# ADC.net
KiCad netlist of a schematic drawn in Altium Designer
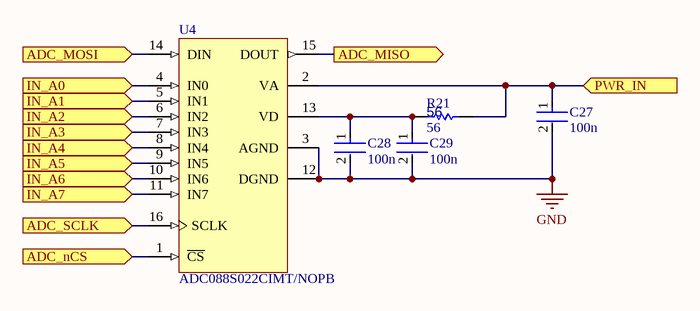
[diagram p0: ADC.SchDoc]

(export (version "E")
  (design (tool "Eeschema 10.0.6"))
  (components
    (comp (ref "C27")
      (value "100n")
      (footprint "FP-0402-L_1_0_0_05-W_0_5-IPC_A")
      (description "LARGE PADS, 0402 CAP, CHANGE COMMENT TO MATCH REAL P/N")
      (libsource (lib "Space Concordia") (part "b4654b650e69147ec39a6b967a45e02"))
    )
    (comp (ref "C28")
      (value "100n")
      (footprint "FP-0402-L_1_0_0_05-W_0_5-IPC_A")
      (description "LARGE PADS, 0402 CAP, CHANGE COMMENT TO MATCH REAL P/N")
      (libsource (lib "Space Concordia") (part "b4654b650e69147ec39a6b967a45e02"))
    )
    (comp (ref "C29")
      (value "100n")
      (footprint "FP-0402-L_1_0_0_05-W_0_5-IPC_A")
      (description "LARGE PADS, 0402 CAP, CHANGE COMMENT TO MATCH REAL P/N")
      (libsource (lib "Space Concordia") (part "b4654b650e69147ec39a6b967a45e02"))
    )
    (comp (ref "R21")
      (value "56")
      (footprint "R0603B")
      (description "Resistor")
      (fields (field (name "ALTIUM_VALUE") "56"))
      (libsource (lib "Space Concordia") (part "Resistor"))
    )
    (comp (ref "U4")
      (value "ADC088S022CIMT/NOPB")
      (footprint "MTC16_L")
      (description "8-Channel, 50 kSPS to 200 kSPS, 8-Bit A/D Converter, 16-pin TSSOP, Pb-Free")
      (fields (field (name "MANUFACTURER") "National Semiconductor"))
      (libsource (lib "Altium Content Vault") (part "CON-ADC-ADC108S052CIMT"))
    )
  )
  (nets
    (net (code "1") (name "/ADC_MISO") (class "Default")
      (node (ref "U4") (pin "15") (pinfunction "DOUT_15") (pintype "output"))
    )
    (net (code "2") (name "/ADC_MOSI") (class "Default")
      (node (ref "U4") (pin "14") (pinfunction "DIN_14") (pintype "input"))
    )
    (net (code "3") (name "/ADC_SCLK") (class "Default")
      (node (ref "U4") (pin "16") (pinfunction "SCLK_16") (pintype "input"))
    )
    (net (code "4") (name "/ADC_nCS") (class "Default")
      (node (ref "U4") (pin "1") (pinfunction "~{CS}_1") (pintype "input"))
    )
    (net (code "5") (name "/IN_A0") (class "Default")
      (node (ref "U4") (pin "4") (pinfunction "IN0_4") (pintype "input"))
    )
    (net (code "6") (name "/IN_A1") (class "Default")
      (node (ref "U4") (pin "5") (pinfunction "IN1_5") (pintype "input"))
    )
    (net (code "7") (name "/IN_A2") (class "Default")
      (node (ref "U4") (pin "6") (pinfunction "IN2_6") (pintype "input"))
    )
    (net (code "8") (name "/IN_A3") (class "Default")
      (node (ref "U4") (pin "7") (pinfunction "IN3_7") (pintype "input"))
    )
    (net (code "9") (name "/IN_A4") (class "Default")
      (node (ref "U4") (pin "8") (pinfunction "IN4_8") (pintype "input"))
    )
    (net (code "10") (name "/IN_A5") (class "Default")
      (node (ref "U4") (pin "9") (pinfunction "IN5_9") (pintype "input"))
    )
    (net (code "11") (name "/IN_A6") (class "Default")
      (node (ref "U4") (pin "10") (pinfunction "IN6_10") (pintype "input"))
    )
    (net (code "12") (name "/IN_A7") (class "Default")
      (node (ref "U4") (pin "11") (pinfunction "IN7_11") (pintype "input"))
    )
    (net (code "13") (name "/PWR_IN") (class "Default")
      (node (ref "C27") (pin "1") (pinfunction "1_1") (pintype "passive"))
      (node (ref "R21") (pin "1") (pinfunction "1_1") (pintype "passive"))
      (node (ref "U4") (pin "2") (pinfunction "VA_2") (pintype "power_in"))
    )
    (net (code "14") (name "GND") (class "Default")
      (node (ref "C27") (pin "2") (pinfunction "2_2") (pintype "passive"))
      (node (ref "C28") (pin "2") (pinfunction "2_2") (pintype "passive"))
      (node (ref "C29") (pin "2") (pinfunction "2_2") (pintype "passive"))
      (node (ref "U4") (pin "12") (pinfunction "DGND_12") (pintype "power_in"))
      (node (ref "U4") (pin "3") (pinfunction "AGND_3") (pintype "power_in"))
    )
    (net (code "15") (name "Net-(U4-VD)") (class "Default")
      (node (ref "C28") (pin "1") (pinfunction "1_1") (pintype "passive"))
      (node (ref "C29") (pin "1") (pinfunction "1_1") (pintype "passive"))
      (node (ref "R21") (pin "2") (pinfunction "2_2") (pintype "passive"))
      (node (ref "U4") (pin "13") (pinfunction "VD_13") (pintype "power_in"))
    )
  )
)
